# design.net
KiCad netlist of a schematic drawn in Altium Designer
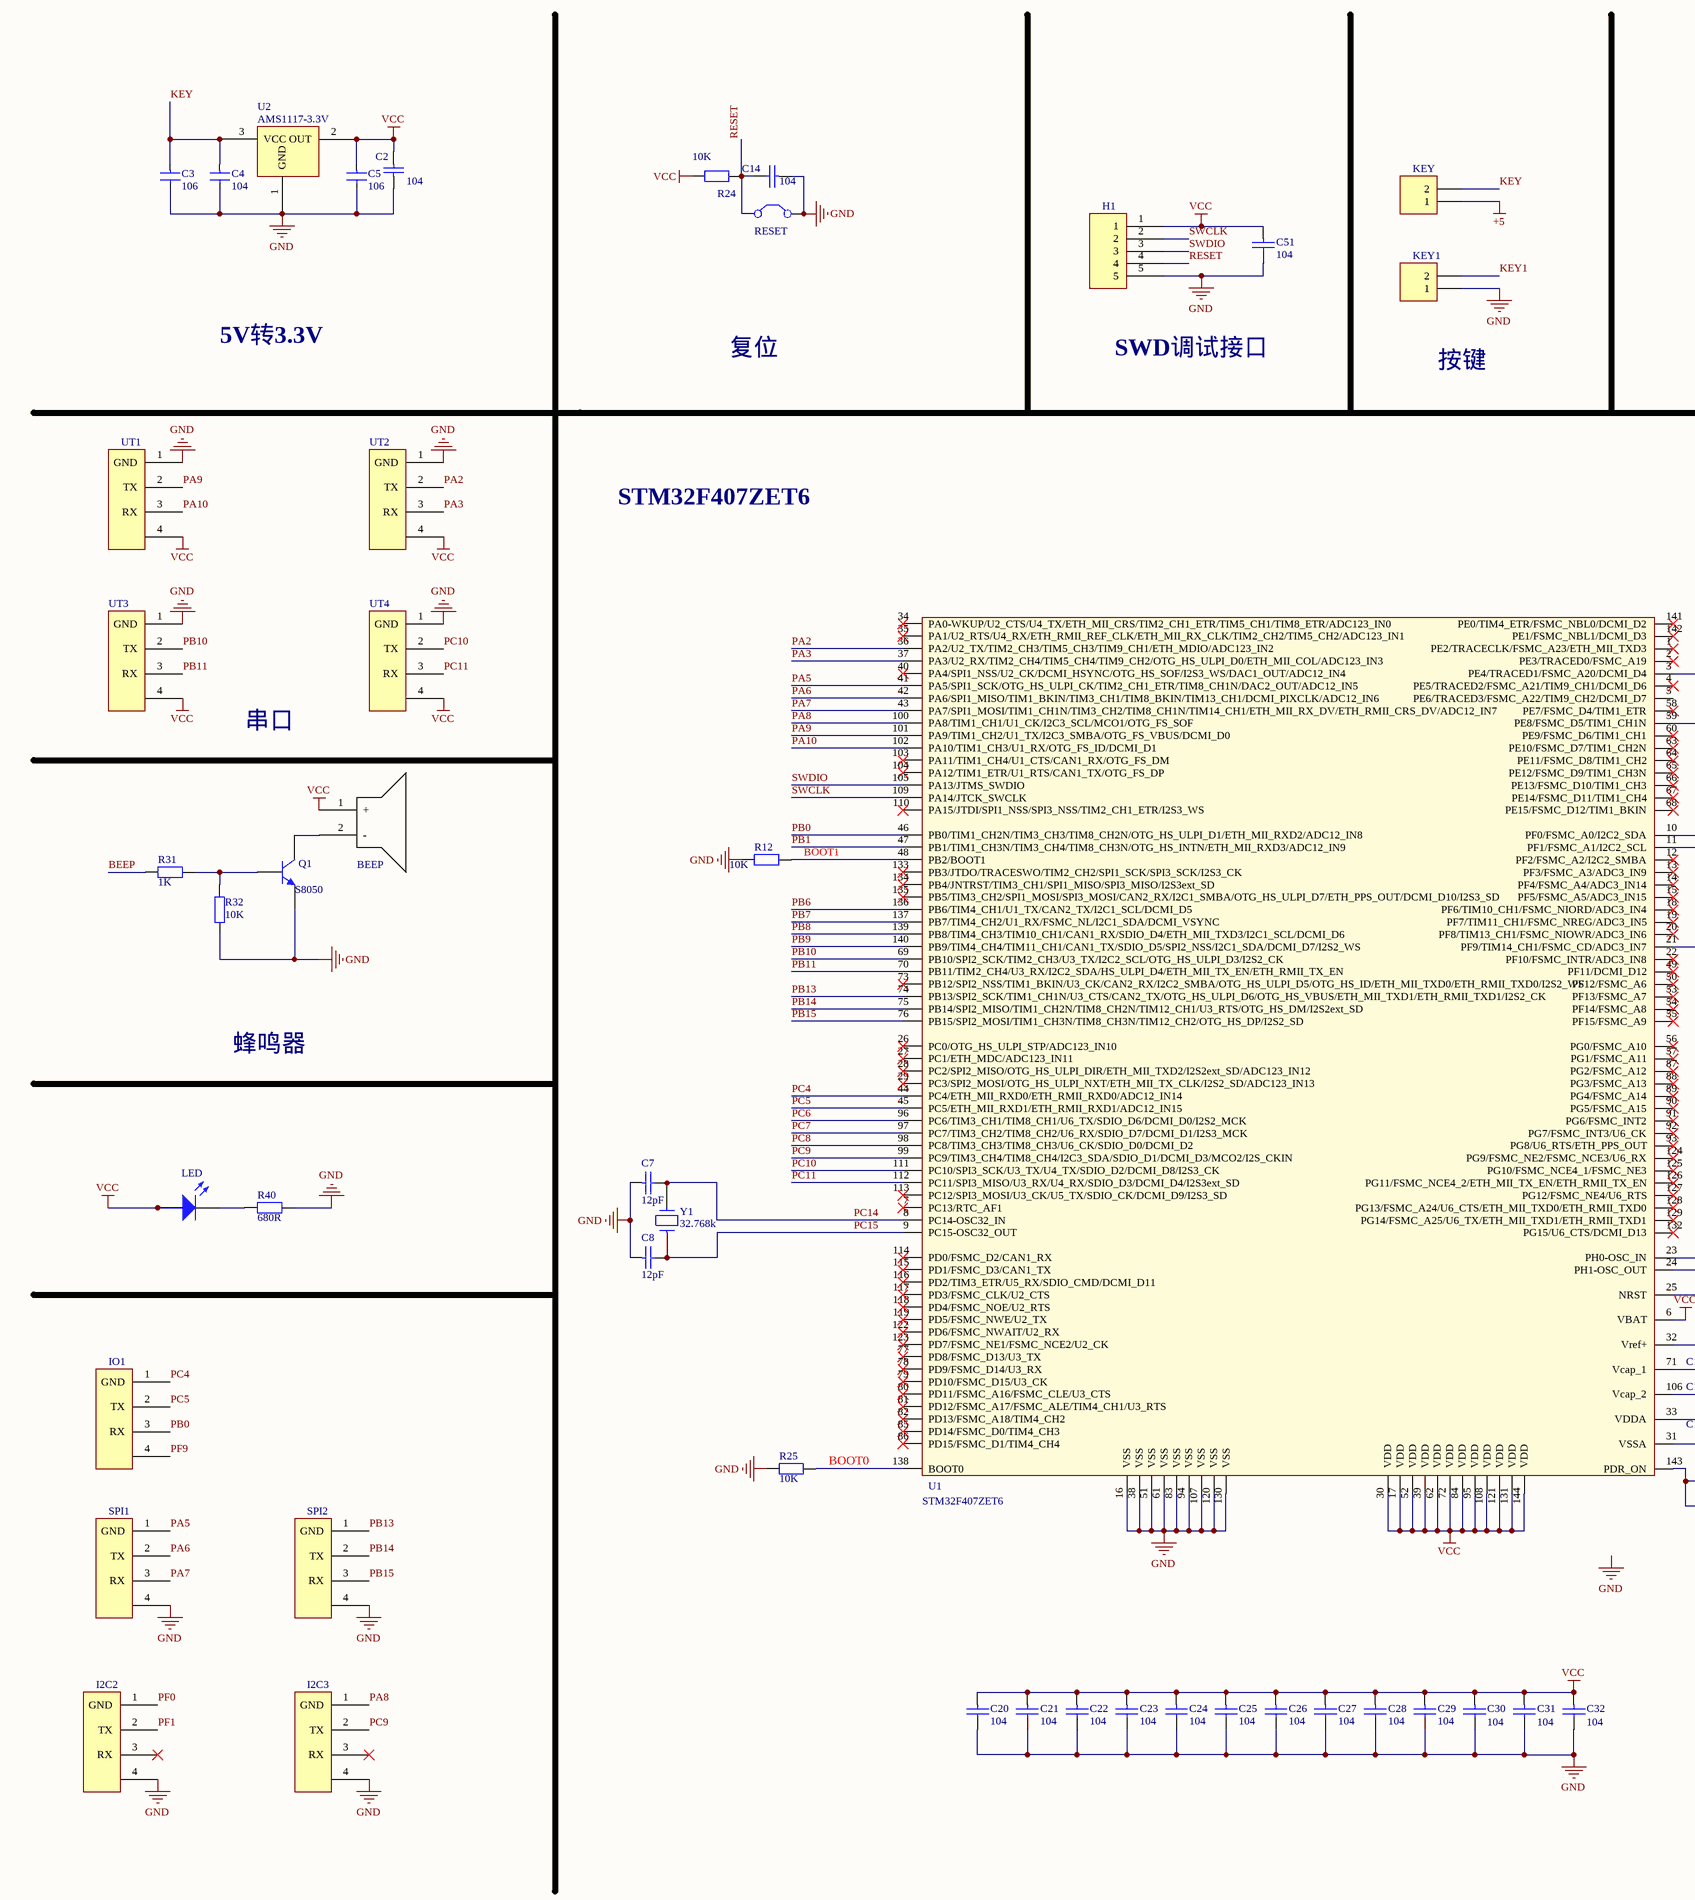
[diagram p0: 垃圾分类.SchDoc, left]
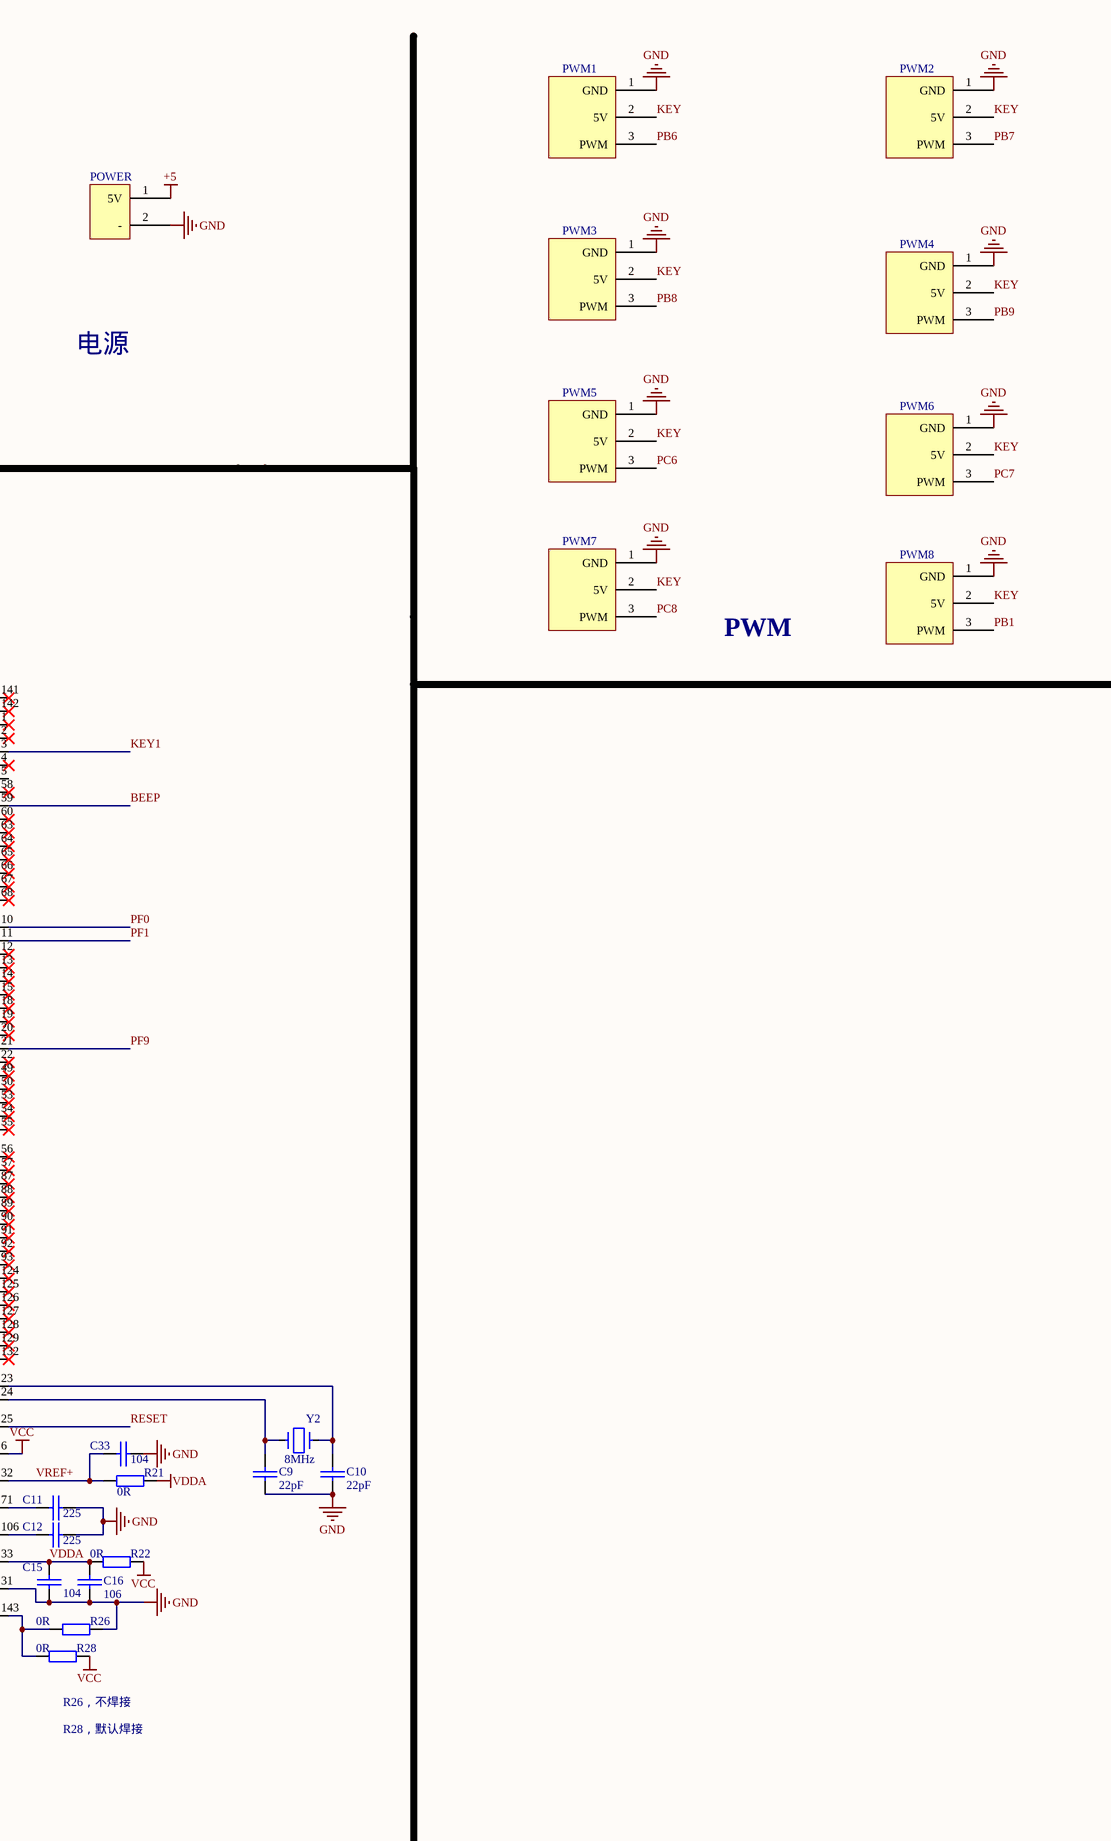
[diagram p1: 垃圾分类.SchDoc, right]

(export (version "E")
  (design (tool "Eeschema 10.0.6"))
  (components
    (comp (ref "BEEP") (value "~") (footprint "蜂鸣器") (libsource (lib "STM32_F407") (part "BEEP")))
    (comp (ref "C2")
      (value "104")
      (footprint "C0805")
      (description "Capacitor")
      (fields (field (name "PUBLISHER") "Altium Limited"))
      (libsource (lib "*") (part "Cap"))
    )
    (comp (ref "C3")
      (value "106")
      (footprint "C0805")
      (description "Capacitor")
      (libsource (lib "电容") (part "0805C"))
    )
    (comp (ref "C4")
      (value "104")
      (footprint "C0805")
      (description "Capacitor")
      (libsource (lib "电容") (part "0805C"))
    )
    (comp (ref "C5")
      (value "106")
      (footprint "C0805")
      (description "Capacitor")
      (libsource (lib "电容") (part "0805C"))
    )
    (comp (ref "C7")
      (value "12pF")
      (footprint "C0805")
      (description "Capcitor")
      (libsource (lib "LXKJSJ") (part "CAP"))
    )
    (comp (ref "C8")
      (value "12pF")
      (footprint "C0805")
      (description "Capcitor")
      (libsource (lib "LXKJSJ") (part "CAP"))
    )
    (comp (ref "C9")
      (value "22pF")
      (footprint "C0805")
      (description "Capcitor")
      (libsource (lib "LXKJSJ") (part "CAP"))
    )
    (comp (ref "C10")
      (value "22pF")
      (footprint "C0805")
      (description "Capcitor")
      (libsource (lib "LXKJSJ") (part "CAP"))
    )
    (comp (ref "C11")
      (value "225")
      (footprint "C0805")
      (description "Capcitor")
      (libsource (lib "LXKJSJ") (part "CAP"))
    )
    (comp (ref "C12")
      (value "225")
      (footprint "C0805")
      (description "Capcitor")
      (libsource (lib "LXKJSJ") (part "CAP"))
    )
    (comp (ref "C14")
      (value "104")
      (footprint "C0805")
      (description "Capcitor")
      (libsource (lib "LXKJSJ") (part "CAP"))
    )
    (comp (ref "C15")
      (value "104")
      (footprint "C0805")
      (description "Capcitor")
      (libsource (lib "LXKJSJ") (part "CAP"))
    )
    (comp (ref "C16")
      (value "106")
      (footprint "C0805")
      (description "Capcitor")
      (libsource (lib "LXKJSJ") (part "CAP"))
    )
    (comp (ref "C20")
      (value "104")
      (footprint "C0805")
      (description "Capcitor")
      (libsource (lib "LXKJSJ") (part "CAP"))
    )
    (comp (ref "C21")
      (value "104")
      (footprint "C0805")
      (description "Capcitor")
      (libsource (lib "LXKJSJ") (part "CAP"))
    )
    (comp (ref "C22")
      (value "104")
      (footprint "C0805")
      (description "Capcitor")
      (libsource (lib "LXKJSJ") (part "CAP"))
    )
    (comp (ref "C23")
      (value "104")
      (footprint "C0805")
      (description "Capcitor")
      (libsource (lib "LXKJSJ") (part "CAP"))
    )
    (comp (ref "C24")
      (value "104")
      (footprint "C0805")
      (description "Capcitor")
      (libsource (lib "LXKJSJ") (part "CAP"))
    )
    (comp (ref "C25")
      (value "104")
      (footprint "C0805")
      (description "Capcitor")
      (libsource (lib "LXKJSJ") (part "CAP"))
    )
    (comp (ref "C26")
      (value "104")
      (footprint "C0805")
      (description "Capcitor")
      (libsource (lib "LXKJSJ") (part "CAP"))
    )
    (comp (ref "C27")
      (value "104")
      (footprint "C0805")
      (description "Capcitor")
      (libsource (lib "LXKJSJ") (part "CAP"))
    )
    (comp (ref "C28")
      (value "104")
      (footprint "C0805")
      (description "Capcitor")
      (libsource (lib "LXKJSJ") (part "CAP"))
    )
    (comp (ref "C29")
      (value "104")
      (footprint "C0805")
      (description "Capcitor")
      (libsource (lib "LXKJSJ") (part "CAP"))
    )
    (comp (ref "C30")
      (value "104")
      (footprint "C0805")
      (description "Capcitor")
      (libsource (lib "LXKJSJ") (part "CAP"))
    )
    (comp (ref "C31")
      (value "104")
      (footprint "C0805")
      (description "Capcitor")
      (libsource (lib "LXKJSJ") (part "CAP"))
    )
    (comp (ref "C32")
      (value "104")
      (footprint "C0805")
      (description "Capcitor")
      (libsource (lib "LXKJSJ") (part "CAP"))
    )
    (comp (ref "C33")
      (value "104")
      (footprint "C0805")
      (description "Capcitor")
      (libsource (lib "LXKJSJ") (part "CAP"))
    )
    (comp (ref "C51")
      (value "104")
      (footprint "C0805")
      (description "Capcitor")
      (libsource (lib "STM32_F407") (part "CAP"))
    )
    (comp (ref "H1") (value "~") (footprint "牛角座2.54-2x5P") (libsource (lib "STM32_F407") (part "SWD")))
    (comp (ref "I2C2")
      (value "~")
      (footprint "GH1.25_4P")
      (libsource (lib "STM32_F407") (part "GH1.25_4P_ckou"))
    )
    (comp (ref "I2C3")
      (value "~")
      (footprint "GH1.25_4P")
      (libsource (lib "STM32_F407") (part "GH1.25_4P_ckou"))
    )
    (comp (ref "IO1")
      (value "~")
      (footprint "GH1.25_4P")
      (libsource (lib "STM32_F407") (part "GH1.25_4P_ckou"))
    )
    (comp (ref "KEY")
      (value "~")
      (footprint "Porwer")
      (description "Header, 2-Pin")
      (fields (field (name "PUBLISHER") "Altium Limited"))
      (libsource (lib "Miscellaneous Connectors") (part "Header 2"))
    )
    (comp (ref "KEY1")
      (value "~")
      (footprint "Porwer")
      (description "Header, 2-Pin")
      (fields (field (name "PUBLISHER") "Altium Limited"))
      (libsource (lib "Miscellaneous Connectors") (part "Header 2"))
    )
    (comp (ref "LED")
      (value "~")
      (footprint "LED0805BLUE")
      (description "Typical RED, GREEN, YELLOW, AMBER GaAs LED")
      (fields (field (name "PUBLISHER") "Altium Limited"))
      (libsource (lib "Miscellaneous Devices") (part "LED2"))
    )
    (comp (ref "POWER") (value "~") (footprint "Porwer") (libsource (lib "STM32_F407") (part "dianyuan")))
    (comp (ref "PWM1") (value "~") (footprint "PWM") (libsource (lib "STM32_F407") (part "pwm")))
    (comp (ref "PWM2") (value "~") (footprint "PWM") (libsource (lib "STM32_F407") (part "pwm")))
    (comp (ref "PWM3") (value "~") (footprint "PWM") (libsource (lib "STM32_F407") (part "pwm")))
    (comp (ref "PWM4") (value "~") (footprint "PWM") (libsource (lib "STM32_F407") (part "pwm")))
    (comp (ref "PWM5") (value "~") (footprint "PWM") (libsource (lib "STM32_F407") (part "pwm")))
    (comp (ref "PWM6") (value "~") (footprint "PWM") (libsource (lib "STM32_F407") (part "pwm")))
    (comp (ref "PWM7") (value "~") (footprint "PWM") (libsource (lib "STM32_F407") (part "pwm")))
    (comp (ref "PWM8") (value "~") (footprint "PWM") (libsource (lib "STM32_F407") (part "pwm")))
    (comp (ref "Q1")
      (value "S8050")
      (footprint "S8050")
      (description "NPN General Purpose Amplifier")
      (fields (field (name "PUBLISHER") "Altium Limited"))
      (libsource (lib "Miscellaneous Devices") (part "2N3904"))
    )
    (comp (ref "R12")
      (value "10K")
      (footprint "R0805")
      (description "Resistor")
      (libsource (lib "Miscellaneous Devices") (part "Res2"))
    )
    (comp (ref "R21")
      (value "0R")
      (footprint "R0805")
      (description "Resistor")
      (libsource (lib "") (part "Res2_1"))
    )
    (comp (ref "R22")
      (value "0R")
      (footprint "R0805")
      (description "Resistor")
      (libsource (lib "") (part "Res2_1"))
    )
    (comp (ref "R24")
      (value "10K")
      (footprint "R0805")
      (description "Resistor")
      (libsource (lib "Miscellaneous Devices") (part "Res2"))
    )
    (comp (ref "R25")
      (value "10K")
      (footprint "R0805")
      (description "Resistor")
      (libsource (lib "") (part "Res2_2"))
    )
    (comp (ref "R26")
      (value "0R")
      (footprint "R0805")
      (description "Resistor")
      (libsource (lib "") (part "Res2_1"))
    )
    (comp (ref "R28")
      (value "0R")
      (footprint "R0805")
      (description "Resistor")
      (libsource (lib "") (part "Res2_1"))
    )
    (comp (ref "R31")
      (value "1K")
      (footprint "R0805")
      (description "Resistor")
      (libsource (lib "") (part "Res2_2"))
    )
    (comp (ref "R32")
      (value "10K")
      (footprint "R0805")
      (description "Resistor")
      (libsource (lib "STM32_F407") (part "Res2"))
    )
    (comp (ref "R40")
      (value "680R")
      (footprint "R0805")
      (description "Resistor")
      (libsource (lib "") (part "Res2_1"))
    )
    (comp (ref "RESET")
      (value "Key")
      (footprint "KEY - duplicate")
      (description "Jumper Wire")
      (fields (field (name "PUBLISHER") "Altium Limited"))
      (libsource (lib "Free Documents") (part "Jumper"))
    )
    (comp (ref "SPI1")
      (value "~")
      (footprint "GH1.25_4P")
      (libsource (lib "STM32_F407") (part "GH1.25_4P_ckou"))
    )
    (comp (ref "SPI2")
      (value "~")
      (footprint "GH1.25_4P")
      (libsource (lib "STM32_F407") (part "GH1.25_4P_ckou"))
    )
    (comp (ref "U1")
      (value "STM32F407ZET6")
      (footprint "LQFP144N")
      (libsource (lib "EXPLORER") (part "STM32F407ZET6"))
    )
    (comp (ref "U2") (value "AMS1117-3.3V") (footprint "ASM1117（yyh）") (libsource (lib "*") (part "11")))
    (comp (ref "UT1")
      (value "~")
      (footprint "GH1.25_4P")
      (libsource (lib "STM32_F407") (part "GH1.25_4P_ckou"))
    )
    (comp (ref "UT2")
      (value "~")
      (footprint "GH1.25_4P")
      (libsource (lib "STM32_F407") (part "GH1.25_4P_ckou"))
    )
    (comp (ref "UT3")
      (value "~")
      (footprint "GH1.25_4P")
      (libsource (lib "STM32_F407") (part "GH1.25_4P_ckou"))
    )
    (comp (ref "UT4")
      (value "~")
      (footprint "GH1.25_4P")
      (libsource (lib "STM32_F407") (part "GH1.25_4P_ckou"))
    )
    (comp (ref "Y1")
      (value "32.768k")
      (footprint "晶振（32.768MHz）")
      (description "Crystal 8MHz PLUG")
      (libsource (lib "*") (part "CRYSTAL"))
    )
    (comp (ref "Y2")
      (value "8MHz")
      (footprint "晶振（8MHz）")
      (description "Crystal Oscillator")
      (libsource (lib "STM32_F407") (part "XTAL"))
    )
  )
  (nets
    (net (code "1") (name "+5") (class "Default")
      (node (ref "KEY") (pin "1") (pinfunction "1_1") (pintype "passive"))
      (node (ref "POWER") (pin "1") (pinfunction "5V_1") (pintype "passive"))
    )
    (net (code "2") (name "/BEEP") (class "Default")
      (node (ref "R31") (pin "1") (pinfunction "1_1") (pintype "passive"))
      (node (ref "U1") (pin "59") (pinfunction "PE8/FSMC_D5/TIM1_CH1N_59") (pintype "passive"))
    )
    (net (code "3") (name "/BOOT0") (class "Default")
      (node (ref "R25") (pin "1") (pinfunction "1_1") (pintype "passive"))
      (node (ref "U1") (pin "138") (pinfunction "BOOT0_138") (pintype "passive"))
    )
    (net (code "4") (name "/BOOT1") (class "Default")
      (node (ref "R12") (pin "1") (pinfunction "1_1") (pintype "passive"))
      (node (ref "U1") (pin "48") (pinfunction "PB2/BOOT1_48") (pintype "passive"))
    )
    (net (code "5") (name "/KEY") (class "Default")
      (node (ref "C3") (pin "1") (pinfunction "1_1") (pintype "passive"))
      (node (ref "C4") (pin "1") (pinfunction "1_1") (pintype "passive"))
      (node (ref "KEY") (pin "2") (pinfunction "2_2") (pintype "passive"))
      (node (ref "PWM1") (pin "2") (pinfunction "5V_2") (pintype "passive"))
      (node (ref "PWM2") (pin "2") (pinfunction "5V_2") (pintype "passive"))
      (node (ref "PWM3") (pin "2") (pinfunction "5V_2") (pintype "passive"))
      (node (ref "PWM4") (pin "2") (pinfunction "5V_2") (pintype "passive"))
      (node (ref "PWM5") (pin "2") (pinfunction "5V_2") (pintype "passive"))
      (node (ref "PWM6") (pin "2") (pinfunction "5V_2") (pintype "passive"))
      (node (ref "PWM7") (pin "2") (pinfunction "5V_2") (pintype "passive"))
      (node (ref "PWM8") (pin "2") (pinfunction "5V_2") (pintype "passive"))
      (node (ref "U2") (pin "3") (pinfunction "VCC_3") (pintype "passive"))
    )
    (net (code "6") (name "/KEY1") (class "Default")
      (node (ref "KEY1") (pin "2") (pinfunction "2_2") (pintype "passive"))
      (node (ref "U1") (pin "3") (pinfunction "PE4/TRACED1/FSMC_A20/DCMI_D4_3") (pintype "passive"))
    )
    (net (code "7") (name "/PA2") (class "Default")
      (node (ref "U1") (pin "36") (pinfunction "PA2/U2_TX/TIM2_CH3/TIM5_CH3/TIM9_CH1/ETH_MDIO/ADC123_IN2_36") (pintype "passive"))
      (node (ref "UT2") (pin "2") (pinfunction "TX_2") (pintype "passive"))
    )
    (net (code "8") (name "/PA3") (class "Default")
      (node (ref "U1") (pin "37") (pinfunction "PA3/U2_RX/TIM2_CH4/TIM5_CH4/TIM9_CH2/OTG_HS_ULPI_D0/ETH_MII_COL/ADC123_IN3_37") (pintype "passive"))
      (node (ref "UT2") (pin "3") (pinfunction "RX_3") (pintype "passive"))
    )
    (net (code "9") (name "/PA5") (class "Default")
      (node (ref "SPI1") (pin "1") (pinfunction "GND_1") (pintype "passive"))
      (node (ref "U1") (pin "41") (pinfunction "PA5/SPI1_SCK/OTG_HS_ULPI_CK/TIM2_CH1_ETR/TIM8_CH1N/DAC2_OUT/ADC12_IN5_41") (pintype "passive"))
    )
    (net (code "10") (name "/PA6") (class "Default")
      (node (ref "SPI1") (pin "2") (pinfunction "TX_2") (pintype "passive"))
      (node (ref "U1") (pin "42") (pinfunction "PA6/SPI1_MISO/TIM1_BKIN/TIM3_CH1/TIM8_BKIN/TIM13_CH1/DCMI_PIXCLK/ADC12_IN6_42") (pintype "passive"))
    )
    (net (code "11") (name "/PA7") (class "Default")
      (node (ref "SPI1") (pin "3") (pinfunction "RX_3") (pintype "passive"))
      (node (ref "U1") (pin "43") (pinfunction "PA7/SPI1_MOSI/TIM1_CH1N/TIM3_CH2/TIM8_CH1N/TIM14_CH1/ETH_MII_RX_DV/ETH_RMII_CRS_DV/ADC12_IN7_43") (pintype "passive"))
    )
    (net (code "12") (name "/PA8") (class "Default")
      (node (ref "I2C3") (pin "1") (pinfunction "GND_1") (pintype "passive"))
      (node (ref "U1") (pin "100") (pinfunction "PA8/TIM1_CH1/U1_CK/I2C3_SCL/MCO1/OTG_FS_SOF_100") (pintype "passive"))
    )
    (net (code "13") (name "/PA9") (class "Default")
      (node (ref "U1") (pin "101") (pinfunction "PA9/TIM1_CH2/U1_TX/I2C3_SMBA/OTG_FS_VBUS/DCMI_D0_101") (pintype "passive"))
      (node (ref "UT1") (pin "2") (pinfunction "TX_2") (pintype "passive"))
    )
    (net (code "14") (name "/PA10") (class "Default")
      (node (ref "U1") (pin "102") (pinfunction "PA10/TIM1_CH3/U1_RX/OTG_FS_ID/DCMI_D1_102") (pintype "passive"))
      (node (ref "UT1") (pin "3") (pinfunction "RX_3") (pintype "passive"))
    )
    (net (code "15") (name "/PB0") (class "Default")
      (node (ref "IO1") (pin "3") (pinfunction "RX_3") (pintype "passive"))
      (node (ref "U1") (pin "46") (pinfunction "PB0/TIM1_CH2N/TIM3_CH3/TIM8_CH2N/OTG_HS_ULPI_D1/ETH_MII_RXD2/ADC12_IN8_46") (pintype "passive"))
    )
    (net (code "16") (name "/PB1") (class "Default")
      (node (ref "PWM8") (pin "3") (pinfunction "PWM_3") (pintype "passive"))
      (node (ref "U1") (pin "47") (pinfunction "PB1/TIM1_CH3N/TIM3_CH4/TIM8_CH3N/OTG_HS_INTN/ETH_MII_RXD3/ADC12_IN9_47") (pintype "passive"))
    )
    (net (code "17") (name "/PB6") (class "Default")
      (node (ref "PWM1") (pin "3") (pinfunction "PWM_3") (pintype "passive"))
      (node (ref "U1") (pin "136") (pinfunction "PB6/TIM4_CH1/U1_TX/CAN2_TX/I2C1_SCL/DCMI_D5_136") (pintype "passive"))
    )
    (net (code "18") (name "/PB7") (class "Default")
      (node (ref "PWM2") (pin "3") (pinfunction "PWM_3") (pintype "passive"))
      (node (ref "U1") (pin "137") (pinfunction "PB7/TIM4_CH2/U1_RX/FSMC_NL/I2C1_SDA/DCMI_VSYNC_137") (pintype "passive"))
    )
    (net (code "19") (name "/PB8") (class "Default")
      (node (ref "PWM3") (pin "3") (pinfunction "PWM_3") (pintype "passive"))
      (node (ref "U1") (pin "139") (pinfunction "PB8/TIM4_CH3/TIM10_CH1/CAN1_RX/SDIO_D4/ETH_MII_TXD3/I2C1_SCL/DCMI_D6_139") (pintype "passive"))
    )
    (net (code "20") (name "/PB9") (class "Default")
      (node (ref "PWM4") (pin "3") (pinfunction "PWM_3") (pintype "passive"))
      (node (ref "U1") (pin "140") (pinfunction "PB9/TIM4_CH4/TIM11_CH1/CAN1_TX/SDIO_D5/SPI2_NSS/I2C1_SDA/DCMI_D7/I2S2_WS_140") (pintype "passive"))
    )
    (net (code "21") (name "/PB10") (class "Default")
      (node (ref "U1") (pin "69") (pinfunction "PB10/SPI2_SCK/TIM2_CH3/U3_TX/I2C2_SCL/OTG_HS_ULPI_D3/I2S2_CK_69") (pintype "passive"))
      (node (ref "UT3") (pin "2") (pinfunction "TX_2") (pintype "passive"))
    )
    (net (code "22") (name "/PB11") (class "Default")
      (node (ref "U1") (pin "70") (pinfunction "PB11/TIM2_CH4/U3_RX/I2C2_SDA/HS_ULPI_D4/ETH_MII_TX_EN/ETH_RMII_TX_EN_70") (pintype "passive"))
      (node (ref "UT3") (pin "3") (pinfunction "RX_3") (pintype "passive"))
    )
    (net (code "23") (name "/PB13") (class "Default")
      (node (ref "SPI2") (pin "1") (pinfunction "GND_1") (pintype "passive"))
      (node (ref "U1") (pin "74") (pinfunction "PB13/SPI2_SCK/TIM1_CH1N/U3_CTS/CAN2_TX/OTG_HS_ULPI_D6/OTG_HS_VBUS/ETH_MII_TXD1/ETH_RMII_TXD1/I2S2_CK_74") (pintype "passive"))
    )
    (net (code "24") (name "/PB14") (class "Default")
      (node (ref "SPI2") (pin "2") (pinfunction "TX_2") (pintype "passive"))
      (node (ref "U1") (pin "75") (pinfunction "PB14/SPI2_MISO/TIM1_CH2N/TIM8_CH2N/TIM12_CH1/U3_RTS/OTG_HS_DM/I2S2ext_SD_75") (pintype "passive"))
    )
    (net (code "25") (name "/PB15") (class "Default")
      (node (ref "SPI2") (pin "3") (pinfunction "RX_3") (pintype "passive"))
      (node (ref "U1") (pin "76") (pinfunction "PB15/SPI2_MOSI/TIM1_CH3N/TIM8_CH3N/TIM12_CH2/OTG_HS_DP/I2S2_SD_76") (pintype "passive"))
    )
    (net (code "26") (name "/PC4") (class "Default")
      (node (ref "IO1") (pin "1") (pinfunction "GND_1") (pintype "passive"))
      (node (ref "U1") (pin "44") (pinfunction "PC4/ETH_MII_RXD0/ETH_RMII_RXD0/ADC12_IN14_44") (pintype "passive"))
    )
    (net (code "27") (name "/PC5") (class "Default")
      (node (ref "IO1") (pin "2") (pinfunction "TX_2") (pintype "passive"))
      (node (ref "U1") (pin "45") (pinfunction "PC5/ETH_MII_RXD1/ETH_RMII_RXD1/ADC12_IN15_45") (pintype "passive"))
    )
    (net (code "28") (name "/PC6") (class "Default")
      (node (ref "PWM5") (pin "3") (pinfunction "PWM_3") (pintype "passive"))
      (node (ref "U1") (pin "96") (pinfunction "PC6/TIM3_CH1/TIM8_CH1/U6_TX/SDIO_D6/DCMI_D0/I2S2_MCK_96") (pintype "passive"))
    )
    (net (code "29") (name "/PC7") (class "Default")
      (node (ref "PWM6") (pin "3") (pinfunction "PWM_3") (pintype "passive"))
      (node (ref "U1") (pin "97") (pinfunction "PC7/TIM3_CH2/TIM8_CH2/U6_RX/SDIO_D7/DCMI_D1/I2S3_MCK_97") (pintype "passive"))
    )
    (net (code "30") (name "/PC8") (class "Default")
      (node (ref "PWM7") (pin "3") (pinfunction "PWM_3") (pintype "passive"))
      (node (ref "U1") (pin "98") (pinfunction "PC8/TIM3_CH3/TIM8_CH3/U6_CK/SDIO_D0/DCMI_D2_98") (pintype "passive"))
    )
    (net (code "31") (name "/PC9") (class "Default")
      (node (ref "I2C3") (pin "2") (pinfunction "TX_2") (pintype "passive"))
      (node (ref "U1") (pin "99") (pinfunction "PC9/TIM3_CH4/TIM8_CH4/I2C3_SDA/SDIO_D1/DCMI_D3/MCO2/I2S_CKIN_99") (pintype "passive"))
    )
    (net (code "32") (name "/PC10") (class "Default")
      (node (ref "U1") (pin "111") (pinfunction "PC10/SPI3_SCK/U3_TX/U4_TX/SDIO_D2/DCMI_D8/I2S3_CK_111") (pintype "passive"))
      (node (ref "UT4") (pin "2") (pinfunction "TX_2") (pintype "passive"))
    )
    (net (code "33") (name "/PC11") (class "Default")
      (node (ref "U1") (pin "112") (pinfunction "PC11/SPI3_MISO/U3_RX/U4_RX/SDIO_D3/DCMI_D4/I2S3ext_SD_112") (pintype "passive"))
      (node (ref "UT4") (pin "3") (pinfunction "RX_3") (pintype "passive"))
    )
    (net (code "34") (name "/PC14") (class "Default")
      (node (ref "C7") (pin "2") (pinfunction "2_2") (pintype "passive"))
      (node (ref "U1") (pin "8") (pinfunction "PC14-OSC32_IN_8") (pintype "passive"))
      (node (ref "Y1") (pin "2") (pinfunction "2_2") (pintype "passive"))
    )
    (net (code "35") (name "/PC15") (class "Default")
      (node (ref "C8") (pin "2") (pinfunction "2_2") (pintype "passive"))
      (node (ref "U1") (pin "9") (pinfunction "PC15-OSC32_OUT_9") (pintype "passive"))
      (node (ref "Y1") (pin "1") (pinfunction "1_1") (pintype "passive"))
    )
    (net (code "36") (name "/PF0") (class "Default")
      (node (ref "I2C2") (pin "1") (pinfunction "GND_1") (pintype "passive"))
      (node (ref "U1") (pin "10") (pinfunction "PF0/FSMC_A0/I2C2_SDA_10") (pintype "passive"))
    )
    (net (code "37") (name "/PF1") (class "Default")
      (node (ref "I2C2") (pin "2") (pinfunction "TX_2") (pintype "passive"))
      (node (ref "U1") (pin "11") (pinfunction "PF1/FSMC_A1/I2C2_SCL_11") (pintype "passive"))
    )
    (net (code "38") (name "/PF9") (class "Default")
      (node (ref "IO1") (pin "4") (pintype "passive"))
      (node (ref "U1") (pin "21") (pinfunction "PF9/TIM14_CH1/FSMC_CD/ADC3_IN7_21") (pintype "passive"))
    )
    (net (code "39") (name "/RESET") (class "Default")
      (node (ref "C14") (pin "2") (pinfunction "2_2") (pintype "passive"))
      (node (ref "H1") (pin "4") (pinfunction "4_4") (pintype "passive"))
      (node (ref "R24") (pin "1") (pinfunction "1_1") (pintype "passive"))
      (node (ref "RESET") (pin "1") (pinfunction "C1_1") (pintype "passive"))
      (node (ref "U1") (pin "25") (pinfunction "NRST_25") (pintype "passive"))
    )
    (net (code "40") (name "/SWCLK") (class "Default")
      (node (ref "H1") (pin "2") (pinfunction "2_2") (pintype "passive"))
      (node (ref "U1") (pin "109") (pinfunction "PA14/JTCK_SWCLK_109") (pintype "passive"))
    )
    (net (code "41") (name "/SWDIO") (class "Default")
      (node (ref "H1") (pin "3") (pinfunction "3_3") (pintype "passive"))
      (node (ref "U1") (pin "105") (pinfunction "PA13/JTMS_SWDIO_105") (pintype "passive"))
    )
    (net (code "42") (name "/VREF+") (class "Default")
      (node (ref "C33") (pin "1") (pinfunction "1_1") (pintype "passive"))
      (node (ref "R21") (pin "1") (pinfunction "1_1") (pintype "passive"))
      (node (ref "U1") (pin "32") (pinfunction "Vref+_32") (pintype "passive"))
    )
    (net (code "43") (name "GND") (class "Default")
      (node (ref "C10") (pin "2") (pinfunction "2_2") (pintype "passive"))
      (node (ref "C11") (pin "2") (pinfunction "2_2") (pintype "passive"))
      (node (ref "C12") (pin "2") (pinfunction "2_2") (pintype "passive"))
      (node (ref "C14") (pin "1") (pinfunction "1_1") (pintype "passive"))
      (node (ref "C15") (pin "1") (pinfunction "1_1") (pintype "passive"))
      (node (ref "C16") (pin "1") (pinfunction "1_1") (pintype "passive"))
      (node (ref "C2") (pin "2") (pinfunction "2_2") (pintype "passive"))
      (node (ref "C20") (pin "2") (pinfunction "2_2") (pintype "passive"))
      (node (ref "C21") (pin "2") (pinfunction "2_2") (pintype "passive"))
      (node (ref "C22") (pin "2") (pinfunction "2_2") (pintype "passive"))
      (node (ref "C23") (pin "2") (pinfunction "2_2") (pintype "passive"))
      (node (ref "C24") (pin "2") (pinfunction "2_2") (pintype "passive"))
      (node (ref "C25") (pin "2") (pinfunction "2_2") (pintype "passive"))
      (node (ref "C26") (pin "2") (pinfunction "2_2") (pintype "passive"))
      (node (ref "C27") (pin "2") (pinfunction "2_2") (pintype "passive"))
      (node (ref "C28") (pin "2") (pinfunction "2_2") (pintype "passive"))
      (node (ref "C29") (pin "2") (pinfunction "2_2") (pintype "passive"))
      (node (ref "C3") (pin "2") (pinfunction "2_2") (pintype "passive"))
      (node (ref "C30") (pin "2") (pinfunction "2_2") (pintype "passive"))
      (node (ref "C31") (pin "2") (pinfunction "2_2") (pintype "passive"))
      (node (ref "C32") (pin "2") (pinfunction "2_2") (pintype "passive"))
      (node (ref "C33") (pin "2") (pinfunction "2_2") (pintype "passive"))
      (node (ref "C4") (pin "2") (pinfunction "2_2") (pintype "passive"))
      (node (ref "C5") (pin "2") (pinfunction "2_2") (pintype "passive"))
      (node (ref "C51") (pin "2") (pinfunction "2_2") (pintype "passive"))
      (node (ref "C7") (pin "1") (pinfunction "1_1") (pintype "passive"))
      (node (ref "C8") (pin "1") (pinfunction "1_1") (pintype "passive"))
      (node (ref "C9") (pin "2") (pinfunction "2_2") (pintype "passive"))
      (node (ref "H1") (pin "5") (pinfunction "5_5") (pintype "passive"))
      (node (ref "I2C2") (pin "4") (pintype "passive"))
      (node (ref "I2C3") (pin "4") (pintype "passive"))
      (node (ref "KEY1") (pin "1") (pinfunction "1_1") (pintype "passive"))
      (node (ref "POWER") (pin "2") (pinfunction "-_2") (pintype "passive"))
      (node (ref "PWM1") (pin "1") (pinfunction "GND_1") (pintype "passive"))
      (node (ref "PWM2") (pin "1") (pinfunction "GND_1") (pintype "passive"))
      (node (ref "PWM3") (pin "1") (pinfunction "GND_1") (pintype "passive"))
      (node (ref "PWM4") (pin "1") (pinfunction "GND_1") (pintype "passive"))
      (node (ref "PWM5") (pin "1") (pinfunction "GND_1") (pintype "passive"))
      (node (ref "PWM6") (pin "1") (pinfunction "GND_1") (pintype "passive"))
      (node (ref "PWM7") (pin "1") (pinfunction "GND_1") (pintype "passive"))
      (node (ref "PWM8") (pin "1") (pinfunction "GND_1") (pintype "passive"))
      (node (ref "Q1") (pin "1") (pinfunction "E_1") (pintype "passive"))
      (node (ref "R12") (pin "2") (pinfunction "2_2") (pintype "passive"))
      (node (ref "R25") (pin "2") (pinfunction "2_2") (pintype "passive"))
      (node (ref "R26") (pin "2") (pinfunction "2_2") (pintype "passive"))
      (node (ref "R32") (pin "1") (pinfunction "1_1") (pintype "passive"))
      (node (ref "R40") (pin "1") (pinfunction "1_1") (pintype "passive"))
      (node (ref "RESET") (pin "2") (pinfunction "C2_2") (pintype "passive"))
      (node (ref "SPI1") (pin "4") (pintype "passive"))
      (node (ref "SPI2") (pin "4") (pintype "passive"))
      (node (ref "U1") (pin "107") (pinfunction "VSS_107") (pintype "passive"))
      (node (ref "U1") (pin "120") (pinfunction "VSS_120") (pintype "passive"))
      (node (ref "U1") (pin "130") (pinfunction "VSS_130") (pintype "passive"))
      (node (ref "U1") (pin "16") (pinfunction "VSS_16") (pintype "passive"))
      (node (ref "U1") (pin "31") (pinfunction "VSSA_31") (pintype "passive"))
      (node (ref "U1") (pin "38") (pinfunction "VSS_38") (pintype "passive"))
      (node (ref "U1") (pin "51") (pinfunction "VSS_51") (pintype "passive"))
      (node (ref "U1") (pin "61") (pinfunction "VSS_61") (pintype "passive"))
      (node (ref "U1") (pin "83") (pinfunction "VSS_83") (pintype "passive"))
      (node (ref "U1") (pin "94") (pinfunction "VSS_94") (pintype "passive"))
      (node (ref "U2") (pin "1") (pinfunction "GND_1") (pintype "passive"))
      (node (ref "UT1") (pin "1") (pinfunction "GND_1") (pintype "passive"))
      (node (ref "UT2") (pin "1") (pinfunction "GND_1") (pintype "passive"))
      (node (ref "UT3") (pin "1") (pinfunction "GND_1") (pintype "passive"))
      (node (ref "UT4") (pin "1") (pinfunction "GND_1") (pintype "passive"))
    )
    (net (code "44") (name "Net-(BEEP--)") (class "Default")
      (node (ref "BEEP") (pin "2") (pinfunction "-_2") (pintype "passive"))
      (node (ref "Q1") (pin "3") (pinfunction "C_3") (pintype "passive"))
    )
    (net (code "45") (name "Net-(LED-K)") (class "Default")
      (node (ref "LED") (pin "2") (pinfunction "K_2") (pintype "passive"))
      (node (ref "R40") (pin "2") (pinfunction "2_2") (pintype "passive"))
    )
    (net (code "46") (name "Net-(Q1-B)") (class "Default")
      (node (ref "Q1") (pin "2") (pinfunction "B_2") (pintype "passive"))
      (node (ref "R31") (pin "2") (pinfunction "2_2") (pintype "passive"))
      (node (ref "R32") (pin "2") (pinfunction "2_2") (pintype "passive"))
    )
    (net (code "47") (name "Net-(U1-PDR_ON)") (class "Default")
      (node (ref "R26") (pin "1") (pinfunction "1_1") (pintype "passive"))
      (node (ref "R28") (pin "1") (pinfunction "1_1") (pintype "passive"))
      (node (ref "U1") (pin "143") (pinfunction "PDR_ON_143") (pintype "passive"))
    )
    (net (code "48") (name "Net-(U1-PH0-OSC_IN)") (class "Default")
      (node (ref "C10") (pin "1") (pinfunction "1_1") (pintype "passive"))
      (node (ref "U1") (pin "23") (pinfunction "PH0-OSC_IN_23") (pintype "passive"))
      (node (ref "Y2") (pin "1") (pinfunction "1_1") (pintype "passive"))
    )
    (net (code "49") (name "Net-(U1-PH1-OSC_OUT)") (class "Default")
      (node (ref "C9") (pin "1") (pinfunction "1_1") (pintype "passive"))
      (node (ref "U1") (pin "24") (pinfunction "PH1-OSC_OUT_24") (pintype "passive"))
      (node (ref "Y2") (pin "2") (pinfunction "2_2") (pintype "passive"))
    )
    (net (code "50") (name "Net-(U1-Vcap_1)") (class "Default")
      (node (ref "C11") (pin "1") (pinfunction "1_1") (pintype "passive"))
      (node (ref "U1") (pin "71") (pinfunction "Vcap_1_71") (pintype "passive"))
    )
    (net (code "51") (name "Net-(U1-Vcap_2)") (class "Default")
      (node (ref "C12") (pin "1") (pinfunction "1_1") (pintype "passive"))
      (node (ref "U1") (pin "106") (pinfunction "Vcap_2_106") (pintype "passive"))
    )
    (net (code "52") (name "VCC") (class "Default")
      (node (ref "BEEP") (pin "1") (pinfunction "+_1") (pintype "passive"))
      (node (ref "C2") (pin "1") (pinfunction "1_1") (pintype "passive"))
      (node (ref "C20") (pin "1") (pinfunction "1_1") (pintype "passive"))
      (node (ref "C21") (pin "1") (pinfunction "1_1") (pintype "passive"))
      (node (ref "C22") (pin "1") (pinfunction "1_1") (pintype "passive"))
      (node (ref "C23") (pin "1") (pinfunction "1_1") (pintype "passive"))
      (node (ref "C24") (pin "1") (pinfunction "1_1") (pintype "passive"))
      (node (ref "C25") (pin "1") (pinfunction "1_1") (pintype "passive"))
      (node (ref "C26") (pin "1") (pinfunction "1_1") (pintype "passive"))
      (node (ref "C27") (pin "1") (pinfunction "1_1") (pintype "passive"))
      (node (ref "C28") (pin "1") (pinfunction "1_1") (pintype "passive"))
      (node (ref "C29") (pin "1") (pinfunction "1_1") (pintype "passive"))
      (node (ref "C30") (pin "1") (pinfunction "1_1") (pintype "passive"))
      (node (ref "C31") (pin "1") (pinfunction "1_1") (pintype "passive"))
      (node (ref "C32") (pin "1") (pinfunction "1_1") (pintype "passive"))
      (node (ref "C5") (pin "1") (pinfunction "1_1") (pintype "passive"))
      (node (ref "C51") (pin "1") (pinfunction "1_1") (pintype "passive"))
      (node (ref "H1") (pin "1") (pinfunction "1_1") (pintype "passive"))
      (node (ref "LED") (pin "1") (pinfunction "A_1") (pintype "passive"))
      (node (ref "R22") (pin "2") (pinfunction "2_2") (pintype "passive"))
      (node (ref "R24") (pin "2") (pinfunction "2_2") (pintype "passive"))
      (node (ref "R28") (pin "2") (pinfunction "2_2") (pintype "passive"))
      (node (ref "U1") (pin "108") (pinfunction "VDD_108") (pintype "passive"))
      (node (ref "U1") (pin "121") (pinfunction "VDD_121") (pintype "passive"))
      (node (ref "U1") (pin "131") (pinfunction "VDD_131") (pintype "passive"))
      (node (ref "U1") (pin "144") (pinfunction "VDD_144") (pintype "passive"))
      (node (ref "U1") (pin "17") (pinfunction "VDD_17") (pintype "passive"))
      (node (ref "U1") (pin "30") (pinfunction "VDD_30") (pintype "passive"))
      (node (ref "U1") (pin "39") (pinfunction "VDD_39") (pintype "passive"))
      (node (ref "U1") (pin "52") (pinfunction "VDD_52") (pintype "passive"))
      (node (ref "U1") (pin "6") (pinfunction "VBAT_6") (pintype "passive"))
      (node (ref "U1") (pin "62") (pinfunction "VDD_62") (pintype "passive"))
      (node (ref "U1") (pin "72") (pinfunction "VDD_72") (pintype "passive"))
      (node (ref "U1") (pin "84") (pinfunction "VDD_84") (pintype "passive"))
      (node (ref "U1") (pin "95") (pinfunction "VDD_95") (pintype "passive"))
      (node (ref "U2") (pin "2") (pinfunction "OUT_2") (pintype "passive"))
      (node (ref "UT1") (pin "4") (pintype "passive"))
      (node (ref "UT2") (pin "4") (pintype "passive"))
      (node (ref "UT3") (pin "4") (pintype "passive"))
      (node (ref "UT4") (pin "4") (pintype "passive"))
    )
    (net (code "53") (name "VDDA") (class "Default")
      (node (ref "C15") (pin "2") (pinfunction "2_2") (pintype "passive"))
      (node (ref "C16") (pin "2") (pinfunction "2_2") (pintype "passive"))
      (node (ref "R21") (pin "2") (pinfunction "2_2") (pintype "passive"))
      (node (ref "R22") (pin "1") (pinfunction "1_1") (pintype "passive"))
      (node (ref "U1") (pin "33") (pinfunction "VDDA_33") (pintype "passive"))
    )
    (net (code "54") (name "unconnected-(I2C2-RX-Pad3)") (class "Default")
      (node (ref "I2C2") (pin "3") (pinfunction "RX_3") (pintype "passive+no_connect"))
    )
    (net (code "55") (name "unconnected-(I2C3-RX-Pad3)") (class "Default")
      (node (ref "I2C3") (pin "3") (pinfunction "RX_3") (pintype "passive+no_connect"))
    )
    (net (code "56") (name "unconnected-(U1-PA0-WKUP{slash}U2_CTS{slash}U4_TX{slash}ETH_MII_CRS{slash}TIM2_CH1_ETR{slash}TIM5_CH1{slash}TIM8_ETR{slash}ADC123_IN0-Pad34)") (class "Default")
      (node (ref "U1") (pin "34") (pinfunction "PA0-WKUP/U2_CTS/U4_TX/ETH_MII_CRS/TIM2_CH1_ETR/TIM5_CH1/TIM8_ETR/ADC123_IN0_34") (pintype "open_collector+no_connect"))
    )
    (net (code "57") (name "unconnected-(U1-PA1{slash}U2_RTS{slash}U4_RX{slash}ETH_RMII_REF_CLK{slash}ETH_MII_RX_CLK{slash}TIM2_CH2{slash}TIM5_CH2{slash}ADC123_IN1-Pad35)") (class "Default")
      (node (ref "U1") (pin "35") (pinfunction "PA1/U2_RTS/U4_RX/ETH_RMII_REF_CLK/ETH_MII_RX_CLK/TIM2_CH2/TIM5_CH2/ADC123_IN1_35") (pintype "passive+no_connect"))
    )
    (net (code "58") (name "unconnected-(U1-PA4{slash}SPI1_NSS{slash}U2_CK{slash}DCMI_HSYNC{slash}OTG_HS_SOF{slash}I2S3_WS{slash}DAC1_OUT{slash}ADC12_IN4-Pad40)") (class "Default")
      (node (ref "U1") (pin "40") (pinfunction "PA4/SPI1_NSS/U2_CK/DCMI_HSYNC/OTG_HS_SOF/I2S3_WS/DAC1_OUT/ADC12_IN4_40") (pintype "passive+no_connect"))
    )
    (net (code "59") (name "unconnected-(U1-PA11{slash}TIM1_CH4{slash}U1_CTS{slash}CAN1_RX{slash}OTG_FS_DM-Pad103)") (class "Default")
      (node (ref "U1") (pin "103") (pinfunction "PA11/TIM1_CH4/U1_CTS/CAN1_RX/OTG_FS_DM_103") (pintype "passive+no_connect"))
    )
    (net (code "60") (name "unconnected-(U1-PA12{slash}TIM1_ETR{slash}U1_RTS{slash}CAN1_TX{slash}OTG_FS_DP-Pad104)") (class "Default")
      (node (ref "U1") (pin "104") (pinfunction "PA12/TIM1_ETR/U1_RTS/CAN1_TX/OTG_FS_DP_104") (pintype "passive+no_connect"))
    )
    (net (code "61") (name "unconnected-(U1-PA15{slash}JTDI{slash}SPI1_NSS{slash}SPI3_NSS{slash}TIM2_CH1_ETR{slash}I2S3_WS-Pad110)") (class "Default")
      (node (ref "U1") (pin "110") (pinfunction "PA15/JTDI/SPI1_NSS/SPI3_NSS/TIM2_CH1_ETR/I2S3_WS_110") (pintype "passive+no_connect"))
    )
    (net (code "62") (name "unconnected-(U1-PB3{slash}JTDO{slash}TRACESWO{slash}TIM2_CH2{slash}SPI1_SCK{slash}SPI3_SCK{slash}I2S3_CK-Pad133)") (class "Default")
      (node (ref "U1") (pin "133") (pinfunction "PB3/JTDO/TRACESWO/TIM2_CH2/SPI1_SCK/SPI3_SCK/I2S3_CK_133") (pintype "passive+no_connect"))
    )
    (net (code "63") (name "unconnected-(U1-PB4{slash}JNTRST{slash}TIM3_CH1{slash}SPI1_MISO{slash}SPI3_MISO{slash}I2S3ext_SD-Pad134)") (class "Default")
      (node (ref "U1") (pin "134") (pinfunction "PB4/JNTRST/TIM3_CH1/SPI1_MISO/SPI3_MISO/I2S3ext_SD_134") (pintype "passive+no_connect"))
    )
    (net (code "64") (name "unconnected-(U1-PB5{slash}TIM3_CH2{slash}SPI1_MOSI{slash}SPI3_MOSI{slash}CAN2_RX{slash}I2C1_SMBA{slash}OTG_HS_ULPI_D7{slash}ETH_PPS_OUT{slash}DCMI_D10{slash}I2S3_SD-Pad135)") (class "Default")
      (node (ref "U1") (pin "135") (pinfunction "PB5/TIM3_CH2/SPI1_MOSI/SPI3_MOSI/CAN2_RX/I2C1_SMBA/OTG_HS_ULPI_D7/ETH_PPS_OUT/DCMI_D10/I2S3_SD_135") (pintype "passive+no_connect"))
    )
    (net (code "65") (name "unconnected-(U1-PB12{slash}SPI2_NSS{slash}TIM1_BKIN{slash}U3_CK{slash}CAN2_RX{slash}I2C2_SMBA{slash}OTG_HS_ULPI_D5{slash}OTG_HS_ID{slash}ETH_MII_TXD0{slash}ETH_RMII_TXD0{slash}I2S2_WS-Pad73)") (class "Default")
      (node (ref "U1") (pin "73") (pinfunction "PB12/SPI2_NSS/TIM1_BKIN/U3_CK/CAN2_RX/I2C2_SMBA/OTG_HS_ULPI_D5/OTG_HS_ID/ETH_MII_TXD0/ETH_RMII_TXD0/I2S2_WS_73") (pintype "passive+no_connect"))
    )
    (net (code "66") (name "unconnected-(U1-PC0{slash}OTG_HS_ULPI_STP{slash}ADC123_IN10-Pad26)") (class "Default")
      (node (ref "U1") (pin "26") (pinfunction "PC0/OTG_HS_ULPI_STP/ADC123_IN10_26") (pintype "passive+no_connect"))
    )
    (net (code "67") (name "unconnected-(U1-PC1{slash}ETH_MDC{slash}ADC123_IN11-Pad27)") (class "Default")
      (node (ref "U1") (pin "27") (pinfunction "PC1/ETH_MDC/ADC123_IN11_27") (pintype "passive+no_connect"))
    )
    (net (code "68") (name "unconnected-(U1-PC2{slash}SPI2_MISO{slash}OTG_HS_ULPI_DIR{slash}ETH_MII_TXD2{slash}I2S2ext_SD{slash}ADC123_IN12-Pad28)") (class "Default")
      (node (ref "U1") (pin "28") (pinfunction "PC2/SPI2_MISO/OTG_HS_ULPI_DIR/ETH_MII_TXD2/I2S2ext_SD/ADC123_IN12_28") (pintype "passive+no_connect"))
    )
    (net (code "69") (name "unconnected-(U1-PC3{slash}SPI2_MOSI{slash}OTG_HS_ULPI_NXT{slash}ETH_MII_TX_CLK{slash}I2S2_SD{slash}ADC123_IN13-Pad29)") (class "Default")
      (node (ref "U1") (pin "29") (pinfunction "PC3/SPI2_MOSI/OTG_HS_ULPI_NXT/ETH_MII_TX_CLK/I2S2_SD/ADC123_IN13_29") (pintype "passive+no_connect"))
    )
    (net (code "70") (name "unconnected-(U1-PC12{slash}SPI3_MOSI{slash}U3_CK{slash}U5_TX{slash}SDIO_CK{slash}DCMI_D9{slash}I2S3_SD-Pad113)") (class "Default")
      (node (ref "U1") (pin "113") (pinfunction "PC12/SPI3_MOSI/U3_CK/U5_TX/SDIO_CK/DCMI_D9/I2S3_SD_113") (pintype "passive+no_connect"))
    )
    (net (code "71") (name "unconnected-(U1-PC13{slash}RTC_AF1-Pad7)") (class "Default")
      (node (ref "U1") (pin "7") (pinfunction "PC13/RTC_AF1_7") (pintype "passive+no_connect"))
    )
    (net (code "72") (name "unconnected-(U1-PD0{slash}FSMC_D2{slash}CAN1_RX-Pad114)") (class "Default")
      (node (ref "U1") (pin "114") (pinfunction "PD0/FSMC_D2/CAN1_RX_114") (pintype "passive+no_connect"))
    )
    (net (code "73") (name "unconnected-(U1-PD1{slash}FSMC_D3{slash}CAN1_TX-Pad115)") (class "Default")
      (node (ref "U1") (pin "115") (pinfunction "PD1/FSMC_D3/CAN1_TX_115") (pintype "passive+no_connect"))
    )
    (net (code "74") (name "unconnected-(U1-PD2{slash}TIM3_ETR{slash}U5_RX{slash}SDIO_CMD{slash}DCMI_D11-Pad116)") (class "Default")
      (node (ref "U1") (pin "116") (pinfunction "PD2/TIM3_ETR/U5_RX/SDIO_CMD/DCMI_D11_116") (pintype "passive+no_connect"))
    )
    (net (code "75") (name "unconnected-(U1-PD3{slash}FSMC_CLK{slash}U2_CTS-Pad117)") (class "Default")
      (node (ref "U1") (pin "117") (pinfunction "PD3/FSMC_CLK/U2_CTS_117") (pintype "passive+no_connect"))
    )
    (net (code "76") (name "unconnected-(U1-PD4{slash}FSMC_NOE{slash}U2_RTS-Pad118)") (class "Default")
      (node (ref "U1") (pin "118") (pinfunction "PD4/FSMC_NOE/U2_RTS_118") (pintype "passive+no_connect"))
    )
    (net (code "77") (name "unconnected-(U1-PD5{slash}FSMC_NWE{slash}U2_TX-Pad119)") (class "Default")
      (node (ref "U1") (pin "119") (pinfunction "PD5/FSMC_NWE/U2_TX_119") (pintype "passive+no_connect"))
    )
    (net (code "78") (name "unconnected-(U1-PD6{slash}FSMC_NWAIT{slash}U2_RX-Pad122)") (class "Default")
      (node (ref "U1") (pin "122") (pinfunction "PD6/FSMC_NWAIT/U2_RX_122") (pintype "passive+no_connect"))
    )
    (net (code "79") (name "unconnected-(U1-PD7{slash}FSMC_NE1{slash}FSMC_NCE2{slash}U2_CK-Pad123)") (class "Default")
      (node (ref "U1") (pin "123") (pinfunction "PD7/FSMC_NE1/FSMC_NCE2/U2_CK_123") (pintype "passive+no_connect"))
    )
    (net (code "80") (name "unconnected-(U1-PD8{slash}FSMC_D13{slash}U3_TX-Pad77)") (class "Default")
      (node (ref "U1") (pin "77") (pinfunction "PD8/FSMC_D13/U3_TX_77") (pintype "passive+no_connect"))
    )
    (net (code "81") (name "unconnected-(U1-PD9{slash}FSMC_D14{slash}U3_RX-Pad78)") (class "Default")
      (node (ref "U1") (pin "78") (pinfunction "PD9/FSMC_D14/U3_RX_78") (pintype "passive+no_connect"))
    )
    (net (code "82") (name "unconnected-(U1-PD10{slash}FSMC_D15{slash}U3_CK-Pad79)") (class "Default")
      (node (ref "U1") (pin "79") (pinfunction "PD10/FSMC_D15/U3_CK_79") (pintype "passive+no_connect"))
    )
    (net (code "83") (name "unconnected-(U1-PD11{slash}FSMC_A16{slash}FSMC_CLE{slash}U3_CTS-Pad80)") (class "Default")
      (node (ref "U1") (pin "80") (pinfunction "PD11/FSMC_A16/FSMC_CLE/U3_CTS_80") (pintype "passive+no_connect"))
    )
    (net (code "84") (name "unconnected-(U1-PD12{slash}FSMC_A17{slash}FSMC_ALE{slash}TIM4_CH1{slash}U3_RTS-Pad81)") (class "Default")
      (node (ref "U1") (pin "81") (pinfunction "PD12/FSMC_A17/FSMC_ALE/TIM4_CH1/U3_RTS_81") (pintype "passive+no_connect"))
    )
    (net (code "85") (name "unconnected-(U1-PD13{slash}FSMC_A18{slash}TIM4_CH2-Pad82)") (class "Default")
      (node (ref "U1") (pin "82") (pinfunction "PD13/FSMC_A18/TIM4_CH2_82") (pintype "passive+no_connect"))
    )
    (net (code "86") (name "unconnected-(U1-PD14{slash}FSMC_D0{slash}TIM4_CH3-Pad85)") (class "Default")
      (node (ref "U1") (pin "85") (pinfunction "PD14/FSMC_D0/TIM4_CH3_85") (pintype "passive+no_connect"))
    )
    (net (code "87") (name "unconnected-(U1-PD15{slash}FSMC_D1{slash}TIM4_CH4-Pad86)") (class "Default")
      (node (ref "U1") (pin "86") (pinfunction "PD15/FSMC_D1/TIM4_CH4_86") (pintype "passive+no_connect"))
    )
    (net (code "88") (name "unconnected-(U1-PE0{slash}TIM4_ETR{slash}FSMC_NBL0{slash}DCMI_D2-Pad141)") (class "Default")
      (node (ref "U1") (pin "141") (pinfunction "PE0/TIM4_ETR/FSMC_NBL0/DCMI_D2_141") (pintype "passive+no_connect"))
    )
    (net (code "89") (name "unconnected-(U1-PE1{slash}FSMC_NBL1{slash}DCMI_D3-Pad142)") (class "Default")
      (node (ref "U1") (pin "142") (pinfunction "PE1/FSMC_NBL1/DCMI_D3_142") (pintype "passive+no_connect"))
    )
    (net (code "90") (name "unconnected-(U1-PE2{slash}TRACECLK{slash}FSMC_A23{slash}ETH_MII_TXD3-Pad1)") (class "Default")
      (node (ref "U1") (pin "1") (pinfunction "PE2/TRACECLK/FSMC_A23/ETH_MII_TXD3_1") (pintype "passive+no_connect"))
    )
    (net (code "91") (name "unconnected-(U1-PE3{slash}TRACED0{slash}FSMC_A19-Pad2)") (class "Default")
      (node (ref "U1") (pin "2") (pinfunction "PE3/TRACED0/FSMC_A19_2") (pintype "passive+no_connect"))
    )
    (net (code "92") (name "unconnected-(U1-PE5{slash}TRACED2{slash}FSMC_A21{slash}TIM9_CH1{slash}DCMI_D6-Pad4)") (class "Default")
      (node (ref "U1") (pin "4") (pinfunction "PE5/TRACED2/FSMC_A21/TIM9_CH1/DCMI_D6_4") (pintype "passive+no_connect"))
    )
    (net (code "93") (name "unconnected-(U1-PE6{slash}TRACED3{slash}FSMC_A22{slash}TIM9_CH2{slash}DCMI_D7-Pad5)") (class "Default")
      (node (ref "U1") (pin "5") (pinfunction "PE6/TRACED3/FSMC_A22/TIM9_CH2/DCMI_D7_5") (pintype "passive"))
    )
    (net (code "94") (name "unconnected-(U1-PE7{slash}FSMC_D4{slash}TIM1_ETR-Pad58)") (class "Default")
      (node (ref "U1") (pin "58") (pinfunction "PE7/FSMC_D4/TIM1_ETR_58") (pintype "passive+no_connect"))
    )
    (net (code "95") (name "unconnected-(U1-PE9{slash}FSMC_D6{slash}TIM1_CH1-Pad60)") (class "Default")
      (node (ref "U1") (pin "60") (pinfunction "PE9/FSMC_D6/TIM1_CH1_60") (pintype "passive+no_connect"))
    )
    (net (code "96") (name "unconnected-(U1-PE10{slash}FSMC_D7{slash}TIM1_CH2N-Pad63)") (class "Default")
      (node (ref "U1") (pin "63") (pinfunction "PE10/FSMC_D7/TIM1_CH2N_63") (pintype "passive+no_connect"))
    )
    (net (code "97") (name "unconnected-(U1-PE11{slash}FSMC_D8{slash}TIM1_CH2-Pad64)") (class "Default")
      (node (ref "U1") (pin "64") (pinfunction "PE11/FSMC_D8/TIM1_CH2_64") (pintype "passive+no_connect"))
    )
    (net (code "98") (name "unconnected-(U1-PE12{slash}FSMC_D9{slash}TIM1_CH3N-Pad65)") (class "Default")
      (node (ref "U1") (pin "65") (pinfunction "PE12/FSMC_D9/TIM1_CH3N_65") (pintype "passive+no_connect"))
    )
    (net (code "99") (name "unconnected-(U1-PE13{slash}FSMC_D10{slash}TIM1_CH3-Pad66)") (class "Default")
      (node (ref "U1") (pin "66") (pinfunction "PE13/FSMC_D10/TIM1_CH3_66") (pintype "passive+no_connect"))
    )
    (net (code "100") (name "unconnected-(U1-PE14{slash}FSMC_D11{slash}TIM1_CH4-Pad67)") (class "Default")
      (node (ref "U1") (pin "67") (pinfunction "PE14/FSMC_D11/TIM1_CH4_67") (pintype "passive+no_connect"))
    )
    (net (code "101") (name "unconnected-(U1-PE15{slash}FSMC_D12{slash}TIM1_BKIN-Pad68)") (class "Default")
      (node (ref "U1") (pin "68") (pinfunction "PE15/FSMC_D12/TIM1_BKIN_68") (pintype "passive+no_connect"))
    )
    (net (code "102") (name "unconnected-(U1-PF2{slash}FSMC_A2{slash}I2C2_SMBA-Pad12)") (class "Default")
      (node (ref "U1") (pin "12") (pinfunction "PF2/FSMC_A2/I2C2_SMBA_12") (pintype "passive+no_connect"))
    )
    (net (code "103") (name "unconnected-(U1-PF3{slash}FSMC_A3{slash}ADC3_IN9-Pad13)") (class "Default")
      (node (ref "U1") (pin "13") (pinfunction "PF3/FSMC_A3/ADC3_IN9_13") (pintype "passive+no_connect"))
    )
    (net (code "104") (name "unconnected-(U1-PF4{slash}FSMC_A4{slash}ADC3_IN14-Pad14)") (class "Default")
      (node (ref "U1") (pin "14") (pinfunction "PF4/FSMC_A4/ADC3_IN14_14") (pintype "passive+no_connect"))
    )
    (net (code "105") (name "unconnected-(U1-PF5{slash}FSMC_A5{slash}ADC3_IN15-Pad15)") (class "Default")
      (node (ref "U1") (pin "15") (pinfunction "PF5/FSMC_A5/ADC3_IN15_15") (pintype "passive+no_connect"))
    )
    (net (code "106") (name "unconnected-(U1-PF6{slash}TIM10_CH1{slash}FSMC_NIORD{slash}ADC3_IN4-Pad18)") (class "Default")
      (node (ref "U1") (pin "18") (pinfunction "PF6/TIM10_CH1/FSMC_NIORD/ADC3_IN4_18") (pintype "passive+no_connect"))
    )
    (net (code "107") (name "unconnected-(U1-PF7{slash}TIM11_CH1{slash}FSMC_NREG{slash}ADC3_IN5-Pad19)") (class "Default")
      (node (ref "U1") (pin "19") (pinfunction "PF7/TIM11_CH1/FSMC_NREG/ADC3_IN5_19") (pintype "passive+no_connect"))
    )
    (net (code "108") (name "unconnected-(U1-PF8{slash}TIM13_CH1{slash}FSMC_NIOWR{slash}ADC3_IN6-Pad20)") (class "Default")
      (node (ref "U1") (pin "20") (pinfunction "PF8/TIM13_CH1/FSMC_NIOWR/ADC3_IN6_20") (pintype "passive+no_connect"))
    )
    (net (code "109") (name "unconnected-(U1-PF10{slash}FSMC_INTR{slash}ADC3_IN8-Pad22)") (class "Default")
      (node (ref "U1") (pin "22") (pinfunction "PF10/FSMC_INTR/ADC3_IN8_22") (pintype "passive+no_connect"))
    )
    (net (code "110") (name "unconnected-(U1-PF11{slash}DCMI_D12-Pad49)") (class "Default")
      (node (ref "U1") (pin "49") (pinfunction "PF11/DCMI_D12_49") (pintype "passive+no_connect"))
    )
    (net (code "111") (name "unconnected-(U1-PF12{slash}FSMC_A6-Pad50)") (class "Default")
      (node (ref "U1") (pin "50") (pinfunction "PF12/FSMC_A6_50") (pintype "passive+no_connect"))
    )
    (net (code "112") (name "unconnected-(U1-PF13{slash}FSMC_A7-Pad53)") (class "Default")
      (node (ref "U1") (pin "53") (pinfunction "PF13/FSMC_A7_53") (pintype "passive+no_connect"))
    )
    (net (code "113") (name "unconnected-(U1-PF14{slash}FSMC_A8-Pad54)") (class "Default")
      (node (ref "U1") (pin "54") (pinfunction "PF14/FSMC_A8_54") (pintype "passive+no_connect"))
    )
    (net (code "114") (name "unconnected-(U1-PF15{slash}FSMC_A9-Pad55)") (class "Default")
      (node (ref "U1") (pin "55") (pinfunction "PF15/FSMC_A9_55") (pintype "passive+no_connect"))
    )
    (net (code "115") (name "unconnected-(U1-PG0{slash}FSMC_A10-Pad56)") (class "Default")
      (node (ref "U1") (pin "56") (pinfunction "PG0/FSMC_A10_56") (pintype "passive+no_connect"))
    )
    (net (code "116") (name "unconnected-(U1-PG1{slash}FSMC_A11-Pad57)") (class "Default")
      (node (ref "U1") (pin "57") (pinfunction "PG1/FSMC_A11_57") (pintype "passive+no_connect"))
    )
    (net (code "117") (name "unconnected-(U1-PG2{slash}FSMC_A12-Pad87)") (class "Default")
      (node (ref "U1") (pin "87") (pinfunction "PG2/FSMC_A12_87") (pintype "passive+no_connect"))
    )
    (net (code "118") (name "unconnected-(U1-PG3{slash}FSMC_A13-Pad88)") (class "Default")
      (node (ref "U1") (pin "88") (pinfunction "PG3/FSMC_A13_88") (pintype "passive+no_connect"))
    )
    (net (code "119") (name "unconnected-(U1-PG4{slash}FSMC_A14-Pad89)") (class "Default")
      (node (ref "U1") (pin "89") (pinfunction "PG4/FSMC_A14_89") (pintype "passive+no_connect"))
    )
    (net (code "120") (name "unconnected-(U1-PG5{slash}FSMC_A15-Pad90)") (class "Default")
      (node (ref "U1") (pin "90") (pinfunction "PG5/FSMC_A15_90") (pintype "passive+no_connect"))
    )
    (net (code "121") (name "unconnected-(U1-PG6{slash}FSMC_INT2-Pad91)") (class "Default")
      (node (ref "U1") (pin "91") (pinfunction "PG6/FSMC_INT2_91") (pintype "passive+no_connect"))
    )
    (net (code "122") (name "unconnected-(U1-PG7{slash}FSMC_INT3{slash}U6_CK-Pad92)") (class "Default")
      (node (ref "U1") (pin "92") (pinfunction "PG7/FSMC_INT3/U6_CK_92") (pintype "passive+no_connect"))
    )
    (net (code "123") (name "unconnected-(U1-PG8{slash}U6_RTS{slash}ETH_PPS_OUT-Pad93)") (class "Default")
      (node (ref "U1") (pin "93") (pinfunction "PG8/U6_RTS/ETH_PPS_OUT_93") (pintype "passive+no_connect"))
    )
    (net (code "124") (name "unconnected-(U1-PG9{slash}FSMC_NE2{slash}FSMC_NCE3{slash}U6_RX-Pad124)") (class "Default")
      (node (ref "U1") (pin "124") (pinfunction "PG9/FSMC_NE2/FSMC_NCE3/U6_RX_124") (pintype "passive+no_connect"))
    )
    (net (code "125") (name "unconnected-(U1-PG10{slash}FSMC_NCE4_1{slash}FSMC_NE3-Pad125)") (class "Default")
      (node (ref "U1") (pin "125") (pinfunction "PG10/FSMC_NCE4_1/FSMC_NE3_125") (pintype "passive+no_connect"))
    )
    (net (code "126") (name "unconnected-(U1-PG11{slash}FSMC_NCE4_2{slash}ETH_MII_TX_EN{slash}ETH_RMII_TX_EN-Pad126)") (class "Default")
      (node (ref "U1") (pin "126") (pinfunction "PG11/FSMC_NCE4_2/ETH_MII_TX_EN/ETH_RMII_TX_EN_126") (pintype "passive+no_connect"))
    )
    (net (code "127") (name "unconnected-(U1-PG12{slash}FSMC_NE4{slash}U6_RTS-Pad127)") (class "Default")
      (node (ref "U1") (pin "127") (pinfunction "PG12/FSMC_NE4/U6_RTS_127") (pintype "passive+no_connect"))
    )
    (net (code "128") (name "unconnected-(U1-PG13{slash}FSMC_A24{slash}U6_CTS{slash}ETH_MII_TXD0{slash}ETH_RMII_TXD0-Pad128)") (class "Default")
      (node (ref "U1") (pin "128") (pinfunction "PG13/FSMC_A24/U6_CTS/ETH_MII_TXD0/ETH_RMII_TXD0_128") (pintype "passive+no_connect"))
    )
    (net (code "129") (name "unconnected-(U1-PG14{slash}FSMC_A25{slash}U6_TX{slash}ETH_MII_TXD1{slash}ETH_RMII_TXD1-Pad129)") (class "Default")
      (node (ref "U1") (pin "129") (pinfunction "PG14/FSMC_A25/U6_TX/ETH_MII_TXD1/ETH_RMII_TXD1_129") (pintype "passive+no_connect"))
    )
    (net (code "130") (name "unconnected-(U1-PG15{slash}U6_CTS{slash}DCMI_D13-Pad132)") (class "Default")
      (node (ref "U1") (pin "132") (pinfunction "PG15/U6_CTS/DCMI_D13_132") (pintype "passive+no_connect"))
    )
  )
)
